# AD5204.net
KiCad netlist of a schematic drawn in EAGLE
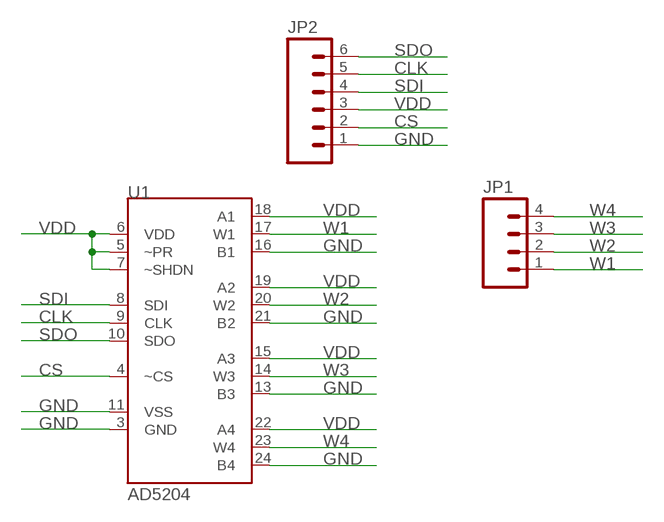
[diagram p0: schematic, sheet 1]

(export (version "E")
  (design (tool "Eeschema 10.0.6"))
  (components
    (comp (ref "JP1")
      (value "M04PTH")
      (footprint "eagle-import:1X04")
      (libsource (lib "eagle-import") (part "M04PTH"))
    )
    (comp (ref "JP2")
      (value "M06SIP")
      (footprint "eagle-import:1X06")
      (libsource (lib "eagle-import") (part "M06SIP"))
    )
    (comp (ref "U1")
      (value "AD5204")
      (footprint "eagle-import:SO24W")
      (libsource (lib "eagle-import") (part "AD5204"))
    )
  )
  (nets
    (net (code "1") (name "/CLK") (class "Default")
      (node (ref "JP2") (pin "5") (pinfunction "5_5") (pintype "passive"))
      (node (ref "U1") (pin "9") (pinfunction "CLK_9") (pintype "bidirectional"))
    )
    (net (code "2") (name "/CS") (class "Default")
      (node (ref "JP2") (pin "2") (pinfunction "2_2") (pintype "passive"))
      (node (ref "U1") (pin "4") (pinfunction "~{CS}_4") (pintype "bidirectional"))
    )
    (net (code "3") (name "/GND") (class "Default")
      (node (ref "JP2") (pin "1") (pinfunction "1_1") (pintype "passive"))
      (node (ref "U1") (pin "11") (pinfunction "VSS_11") (pintype "bidirectional"))
      (node (ref "U1") (pin "13") (pinfunction "B3_13") (pintype "bidirectional"))
      (node (ref "U1") (pin "16") (pinfunction "B1_16") (pintype "bidirectional"))
      (node (ref "U1") (pin "21") (pinfunction "B2_21") (pintype "bidirectional"))
      (node (ref "U1") (pin "24") (pinfunction "B4_24") (pintype "bidirectional"))
      (node (ref "U1") (pin "3") (pinfunction "GND_3") (pintype "bidirectional"))
    )
    (net (code "4") (name "/SDI") (class "Default")
      (node (ref "JP2") (pin "4") (pinfunction "4_4") (pintype "passive"))
      (node (ref "U1") (pin "8") (pinfunction "SDI_8") (pintype "bidirectional"))
    )
    (net (code "5") (name "/SDO") (class "Default")
      (node (ref "JP2") (pin "6") (pinfunction "6_6") (pintype "passive"))
      (node (ref "U1") (pin "10") (pinfunction "SDO_10") (pintype "bidirectional"))
    )
    (net (code "6") (name "/VDD") (class "Default")
      (node (ref "JP2") (pin "3") (pinfunction "3_3") (pintype "passive"))
      (node (ref "U1") (pin "15") (pinfunction "A3_15") (pintype "bidirectional"))
      (node (ref "U1") (pin "18") (pinfunction "A1_18") (pintype "bidirectional"))
      (node (ref "U1") (pin "19") (pinfunction "A2_19") (pintype "bidirectional"))
      (node (ref "U1") (pin "22") (pinfunction "A4_22") (pintype "bidirectional"))
      (node (ref "U1") (pin "5") (pinfunction "~{PR}_5") (pintype "bidirectional"))
      (node (ref "U1") (pin "6") (pinfunction "VDD_6") (pintype "bidirectional"))
      (node (ref "U1") (pin "7") (pinfunction "~{SHDN}_7") (pintype "bidirectional"))
    )
    (net (code "7") (name "/W1") (class "Default")
      (node (ref "JP1") (pin "1") (pinfunction "1_1") (pintype "passive"))
      (node (ref "U1") (pin "17") (pinfunction "W1_17") (pintype "bidirectional"))
    )
    (net (code "8") (name "/W2") (class "Default")
      (node (ref "JP1") (pin "2") (pinfunction "2_2") (pintype "passive"))
      (node (ref "U1") (pin "20") (pinfunction "W2_20") (pintype "bidirectional"))
    )
    (net (code "9") (name "/W3") (class "Default")
      (node (ref "JP1") (pin "3") (pinfunction "3_3") (pintype "passive"))
      (node (ref "U1") (pin "14") (pinfunction "W3_14") (pintype "bidirectional"))
    )
    (net (code "10") (name "/W4") (class "Default")
      (node (ref "JP1") (pin "4") (pinfunction "4_4") (pintype "passive"))
      (node (ref "U1") (pin "23") (pinfunction "W4_23") (pintype "bidirectional"))
    )
  )
)
